# Panorama.net
KiCad netlist of a schematic drawn in Altium Designer
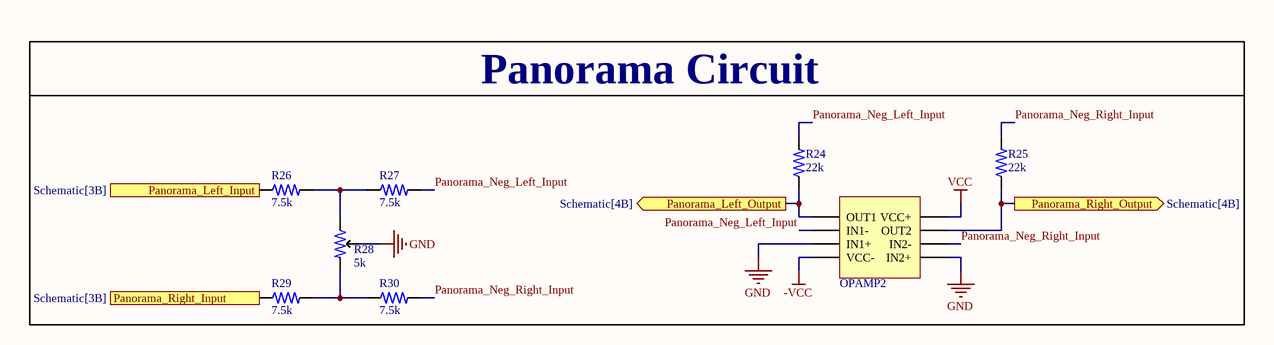
[diagram p0: Panorama.SchDoc]

(export (version "E")
  (design (tool "Eeschema 10.0.6"))
  (components
    (comp (ref "OPAMP2")
      (value "TL072")
      (footprint "DIP8")
      (libsource (lib "AltiumLibrary-Mugetsu") (part "TL072"))
    )
    (comp (ref "R24")
      (value "22k")
      (footprint "RES0603")
      (fields (field (name "MP") "3-1879460-6"))
      (libsource (lib "AltiumLibrary-Mugetsu") (part "RESISTOR SMD"))
    )
    (comp (ref "R25")
      (value "22k")
      (footprint "RES0603")
      (fields (field (name "MP") "3-1879460-6"))
      (libsource (lib "AltiumLibrary-Mugetsu") (part "RESISTOR SMD"))
    )
    (comp (ref "R26")
      (value "7.5k")
      (footprint "RES0603")
      (fields (field (name "MP") "3-1879460-6"))
      (libsource (lib "AltiumLibrary-Mugetsu") (part "RESISTOR SMD"))
    )
    (comp (ref "R27")
      (value "7.5k")
      (footprint "RES0603")
      (fields (field (name "MP") "3-1879460-6"))
      (libsource (lib "AltiumLibrary-Mugetsu") (part "RESISTOR SMD"))
    )
    (comp (ref "R28")
      (value "5k")
      (footprint "Potentiometer THT")
      (libsource (lib "AltiumLibrary-Mugetsu") (part "Potentiometer"))
    )
    (comp (ref "R29")
      (value "7.5k")
      (footprint "RES0603")
      (fields (field (name "MP") "3-1879460-6"))
      (libsource (lib "AltiumLibrary-Mugetsu") (part "RESISTOR SMD"))
    )
    (comp (ref "R30")
      (value "7.5k")
      (footprint "RES0603")
      (fields (field (name "MP") "3-1879460-6"))
      (libsource (lib "AltiumLibrary-Mugetsu") (part "RESISTOR SMD"))
    )
  )
  (nets
    (net (code "1") (name "-VCC") (class "Default")
      (node (ref "OPAMP2") (pin "4") (pinfunction "VCC-_4") (pintype "passive"))
    )
    (net (code "2") (name "/Panorama_Left_Input") (class "Default")
      (node (ref "R26") (pin "1") (pinfunction "1_1") (pintype "passive"))
    )
    (net (code "3") (name "/Panorama_Left_Output") (class "Default")
      (node (ref "OPAMP2") (pin "1") (pinfunction "OUT1_1") (pintype "passive"))
      (node (ref "R24") (pin "1") (pinfunction "1_1") (pintype "passive"))
    )
    (net (code "4") (name "/Panorama_Neg_Left_Input") (class "Default")
      (node (ref "OPAMP2") (pin "2") (pinfunction "IN1-_2") (pintype "passive"))
      (node (ref "R24") (pin "2") (pinfunction "2_2") (pintype "passive"))
      (node (ref "R27") (pin "2") (pinfunction "2_2") (pintype "passive"))
    )
    (net (code "5") (name "/Panorama_Neg_Right_Input") (class "Default")
      (node (ref "OPAMP2") (pin "6") (pinfunction "IN2-_6") (pintype "passive"))
      (node (ref "R25") (pin "2") (pinfunction "2_2") (pintype "passive"))
      (node (ref "R30") (pin "2") (pinfunction "2_2") (pintype "passive"))
    )
    (net (code "6") (name "/Panorama_Right_Input") (class "Default")
      (node (ref "R29") (pin "1") (pinfunction "1_1") (pintype "passive"))
    )
    (net (code "7") (name "/Panorama_Right_Output") (class "Default")
      (node (ref "OPAMP2") (pin "7") (pinfunction "OUT2_7") (pintype "passive"))
      (node (ref "R25") (pin "1") (pinfunction "1_1") (pintype "passive"))
    )
    (net (code "8") (name "GND") (class "Default")
      (node (ref "OPAMP2") (pin "3") (pinfunction "IN1+_3") (pintype "passive"))
      (node (ref "OPAMP2") (pin "5") (pinfunction "IN2+_5") (pintype "passive"))
      (node (ref "R28") (pin "3") (pinfunction "3_3") (pintype "passive"))
    )
    (net (code "9") (name "Net-(R26-Pad2)") (class "Default")
      (node (ref "R26") (pin "2") (pinfunction "2_2") (pintype "passive"))
      (node (ref "R27") (pin "1") (pinfunction "1_1") (pintype "passive"))
      (node (ref "R28") (pin "1") (pinfunction "1_1") (pintype "passive"))
    )
    (net (code "10") (name "Net-(R28-Pad2)") (class "Default")
      (node (ref "R28") (pin "2") (pinfunction "2_2") (pintype "passive"))
      (node (ref "R29") (pin "2") (pinfunction "2_2") (pintype "passive"))
      (node (ref "R30") (pin "1") (pinfunction "1_1") (pintype "passive"))
    )
    (net (code "11") (name "VCC") (class "Default")
      (node (ref "OPAMP2") (pin "8") (pinfunction "VCC+_8") (pintype "passive"))
    )
  )
)
